# LLS.net
KiCad netlist of a schematic drawn in Altium Designer
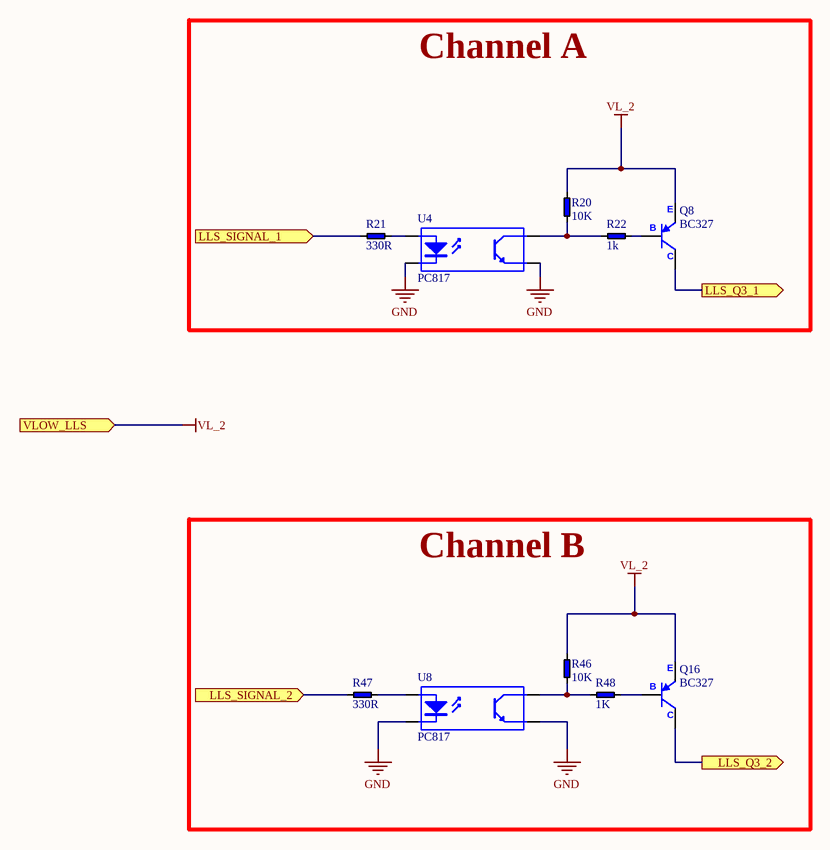
[diagram p0: LLS.SchDoc]

(export (version "E")
  (design (tool "Eeschema 10.0.6"))
  (components
    (comp (ref "Q8")
      (value "BC327")
      (footprint "Transistor - duplicate3")
      (libsource (lib "Altium_Abbas") (part "PNP"))
    )
    (comp (ref "Q16")
      (value "BC327")
      (footprint "Transistor - duplicate3")
      (libsource (lib "Altium_Abbas") (part "PNP"))
    )
    (comp (ref "R20")
      (value "10K")
      (footprint "RESISTOR _9")
      (libsource (lib "Altium_Abbas") (part "RESISTOR"))
    )
    (comp (ref "R21")
      (value "330R")
      (footprint "RESISTOR _9")
      (libsource (lib "Altium_Abbas") (part "RESISTOR"))
    )
    (comp (ref "R22")
      (value "1k")
      (footprint "RESISTOR _9")
      (libsource (lib "Altium_Abbas") (part "RESISTOR"))
    )
    (comp (ref "R46")
      (value "10K")
      (footprint "RESISTOR _9")
      (libsource (lib "Altium_Abbas") (part "RESISTOR"))
    )
    (comp (ref "R47")
      (value "330R")
      (footprint "RESISTOR _9")
      (libsource (lib "Altium_Abbas") (part "RESISTOR"))
    )
    (comp (ref "R48")
      (value "1K")
      (footprint "RESISTOR _9")
      (libsource (lib "Altium_Abbas") (part "RESISTOR"))
    )
    (comp (ref "U4")
      (value "PC817")
      (footprint "IC X4 PIN")
      (description "4-Pin Phototransistor Optocoupler")
      (fields (field (name "PUBLISHER") "Altium Limited"))
      (libsource (lib "Altium_Abbas") (part "Opto-coupler"))
    )
    (comp (ref "U8")
      (value "PC817")
      (footprint "IC X4 PIN")
      (description "4-Pin Phototransistor Optocoupler")
      (fields (field (name "PUBLISHER") "Altium Limited"))
      (libsource (lib "Altium_Abbas") (part "Opto-coupler"))
    )
  )
  (nets
    (net (code "1") (name "/LLS_Q3_1") (class "Default")
      (node (ref "Q8") (pin "3") (pinfunction "C_3") (pintype "passive"))
    )
    (net (code "2") (name "/LLS_Q3_2") (class "Default")
      (node (ref "Q16") (pin "3") (pinfunction "C_3") (pintype "passive"))
    )
    (net (code "3") (name "/LLS_SIGNAL_1") (class "Default")
      (node (ref "R21") (pin "1") (pinfunction "5_1") (pintype "passive"))
    )
    (net (code "4") (name "/LLS_SIGNAL_2") (class "Default")
      (node (ref "R47") (pin "1") (pinfunction "5_1") (pintype "passive"))
    )
    (net (code "5") (name "GND") (class "Default")
      (node (ref "U4") (pin "2") (pinfunction "K_2") (pintype "passive"))
      (node (ref "U4") (pin "3") (pinfunction "E_3") (pintype "passive"))
      (node (ref "U8") (pin "2") (pinfunction "K_2") (pintype "passive"))
      (node (ref "U8") (pin "3") (pinfunction "E_3") (pintype "passive"))
    )
    (net (code "6") (name "Net-(Q8-B)") (class "Default")
      (node (ref "Q8") (pin "2") (pinfunction "B_2") (pintype "passive"))
      (node (ref "R22") (pin "2") (pinfunction "6_2") (pintype "passive"))
    )
    (net (code "7") (name "Net-(Q16-B)") (class "Default")
      (node (ref "Q16") (pin "2") (pinfunction "B_2") (pintype "passive"))
      (node (ref "R48") (pin "2") (pinfunction "6_2") (pintype "passive"))
    )
    (net (code "8") (name "Net-(R20-5)") (class "Default")
      (node (ref "R20") (pin "1") (pinfunction "5_1") (pintype "passive"))
      (node (ref "R22") (pin "1") (pinfunction "5_1") (pintype "passive"))
      (node (ref "U4") (pin "4") (pinfunction "C_4") (pintype "passive"))
    )
    (net (code "9") (name "Net-(R21-6)") (class "Default")
      (node (ref "R21") (pin "2") (pinfunction "6_2") (pintype "passive"))
      (node (ref "U4") (pin "1") (pinfunction "A_1") (pintype "passive"))
    )
    (net (code "10") (name "Net-(R46-5)") (class "Default")
      (node (ref "R46") (pin "1") (pinfunction "5_1") (pintype "passive"))
      (node (ref "R48") (pin "1") (pinfunction "5_1") (pintype "passive"))
      (node (ref "U8") (pin "4") (pinfunction "C_4") (pintype "passive"))
    )
    (net (code "11") (name "Net-(R47-6)") (class "Default")
      (node (ref "R47") (pin "2") (pinfunction "6_2") (pintype "passive"))
      (node (ref "U8") (pin "1") (pinfunction "A_1") (pintype "passive"))
    )
    (net (code "12") (name "VL_2") (class "Default")
      (node (ref "Q16") (pin "1") (pinfunction "E_1") (pintype "passive"))
      (node (ref "Q8") (pin "1") (pinfunction "E_1") (pintype "passive"))
      (node (ref "R20") (pin "2") (pinfunction "6_2") (pintype "passive"))
      (node (ref "R46") (pin "2") (pinfunction "6_2") (pintype "passive"))
    )
  )
)
